# ports.net
KiCad netlist of a schematic drawn in Altium Designer
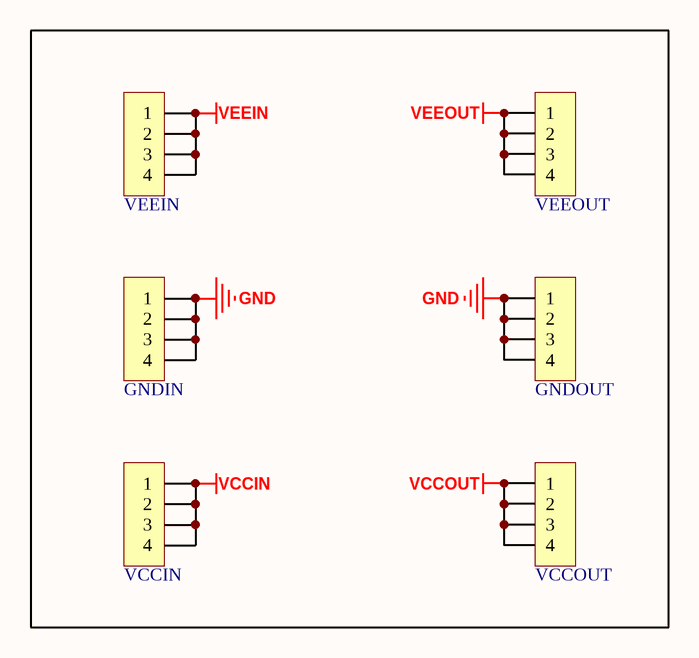
[diagram p0: ports.SchDoc]

(export (version "E")
  (design (tool "Eeschema 10.0.6"))
  (components
    (comp (ref "GNDIN")
      (value "HDR-1X4")
      (footprint "HDR2.54-LI-4P")
      (description "4P接插件")
      (fields (field (name "版权归属") "源创客"))
      (libsource (lib "") (part "Header 4_1"))
    )
    (comp (ref "GNDOUT")
      (value "HDR-1X4")
      (footprint "HDR2.54-LI-4P")
      (description "4P接插件")
      (fields (field (name "版权归属") "源创客"))
      (libsource (lib "IL") (part "Header 4"))
    )
    (comp (ref "VCCIN")
      (value "HDR-1X4")
      (footprint "HDR2.54-LI-4P")
      (description "4P接插件")
      (fields (field (name "版权归属") "源创客"))
      (libsource (lib "") (part "Header 4_1"))
    )
    (comp (ref "VCCOUT")
      (value "HDR-1X4")
      (footprint "HDR2.54-LI-4P")
      (description "4P接插件")
      (fields (field (name "版权归属") "源创客"))
      (libsource (lib "IL") (part "Header 4"))
    )
    (comp (ref "VEEIN")
      (value "HDR-1X4")
      (footprint "HDR2.54-LI-4P")
      (description "4P接插件")
      (fields (field (name "版权归属") "源创客"))
      (libsource (lib "") (part "Header 4_1"))
    )
    (comp (ref "VEEOUT")
      (value "HDR-1X4")
      (footprint "HDR2.54-LI-4P")
      (description "4P接插件")
      (fields (field (name "版权归属") "源创客"))
      (libsource (lib "IL") (part "Header 4"))
    )
  )
  (nets
    (net (code "1") (name "GND") (class "Default")
      (node (ref "GNDIN") (pin "1") (pinfunction "1_1") (pintype "passive"))
      (node (ref "GNDIN") (pin "2") (pinfunction "2_2") (pintype "passive"))
      (node (ref "GNDIN") (pin "3") (pinfunction "3_3") (pintype "passive"))
      (node (ref "GNDIN") (pin "4") (pinfunction "4_4") (pintype "passive"))
      (node (ref "GNDOUT") (pin "1") (pinfunction "1_1") (pintype "passive"))
      (node (ref "GNDOUT") (pin "2") (pinfunction "2_2") (pintype "passive"))
      (node (ref "GNDOUT") (pin "3") (pinfunction "3_3") (pintype "passive"))
      (node (ref "GNDOUT") (pin "4") (pinfunction "4_4") (pintype "passive"))
    )
    (net (code "2") (name "VCCIN") (class "Default")
      (node (ref "VCCIN") (pin "1") (pinfunction "1_1") (pintype "passive"))
      (node (ref "VCCIN") (pin "2") (pinfunction "2_2") (pintype "passive"))
      (node (ref "VCCIN") (pin "3") (pinfunction "3_3") (pintype "passive"))
      (node (ref "VCCIN") (pin "4") (pinfunction "4_4") (pintype "passive"))
    )
    (net (code "3") (name "VCCOUT") (class "Default")
      (node (ref "VCCOUT") (pin "1") (pinfunction "1_1") (pintype "passive"))
      (node (ref "VCCOUT") (pin "2") (pinfunction "2_2") (pintype "passive"))
      (node (ref "VCCOUT") (pin "3") (pinfunction "3_3") (pintype "passive"))
      (node (ref "VCCOUT") (pin "4") (pinfunction "4_4") (pintype "passive"))
    )
    (net (code "4") (name "VEEIN") (class "Default")
      (node (ref "VEEIN") (pin "1") (pinfunction "1_1") (pintype "passive"))
      (node (ref "VEEIN") (pin "2") (pinfunction "2_2") (pintype "passive"))
      (node (ref "VEEIN") (pin "3") (pinfunction "3_3") (pintype "passive"))
      (node (ref "VEEIN") (pin "4") (pinfunction "4_4") (pintype "passive"))
    )
    (net (code "5") (name "VEEOUT") (class "Default")
      (node (ref "VEEOUT") (pin "1") (pinfunction "1_1") (pintype "passive"))
      (node (ref "VEEOUT") (pin "2") (pinfunction "2_2") (pintype "passive"))
      (node (ref "VEEOUT") (pin "3") (pinfunction "3_3") (pintype "passive"))
      (node (ref "VEEOUT") (pin "4") (pinfunction "4_4") (pintype "passive"))
    )
  )
)
